# Main.net
KiCad netlist of a schematic drawn in Altium Designer
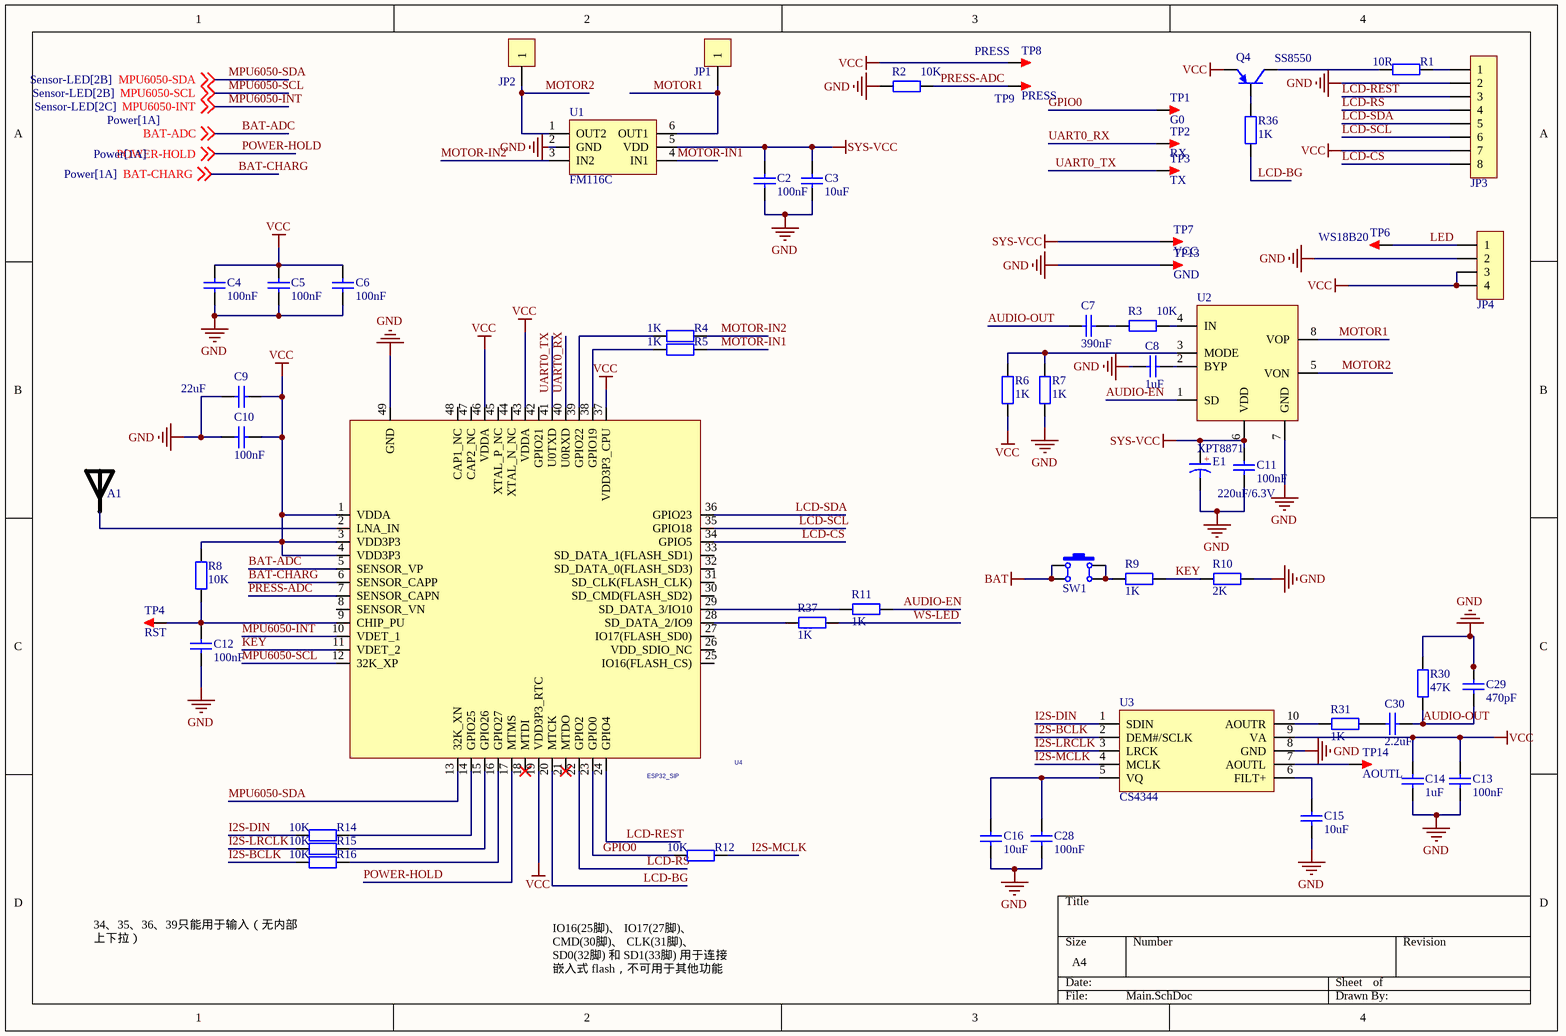
[diagram p0: Main.SchDoc]

(export (version "E")
  (design (tool "Eeschema 10.0.6"))
  (components
    (comp (ref "A1")
      (value "RAINSUN")
      (footprint "ANT-Rainsun-AN5120")
      (libsource (lib "1.7 - WiFi天线-SMA射频座") (part "ANT-Rainsun-AP5120"))
    )
    (comp (ref "C2")
      (value "100nF")
      (footprint "C0402_M")
      (description "贴片电容/MLCC电容")
      (libsource (lib "0.1 - 电阻-电容-电感-晶振-晶体-磁珠-电位器-法拉电容-馈通电容") (part "C"))
    )
    (comp (ref "C3")
      (value "10uF")
      (footprint "C0402_M")
      (description "贴片电容/MLCC电容")
      (libsource (lib "0.1 - 电阻-电容-电感-晶振-晶体-磁珠-电位器-法拉电容-馈通电容") (part "C"))
    )
    (comp (ref "C4")
      (value "100nF")
      (footprint "C0402_M")
      (description "贴片电容/MLCC电容")
      (libsource (lib "0.1 - 电阻-电容-电感-晶振-晶体-磁珠-电位器-法拉电容-馈通电容") (part "C"))
    )
    (comp (ref "C5")
      (value "100nF")
      (footprint "C0402_M")
      (description "贴片电容/MLCC电容")
      (libsource (lib "0.1 - 电阻-电容-电感-晶振-晶体-磁珠-电位器-法拉电容-馈通电容") (part "C"))
    )
    (comp (ref "C6")
      (value "100nF")
      (footprint "C0402_M")
      (description "贴片电容/MLCC电容")
      (libsource (lib "0.1 - 电阻-电容-电感-晶振-晶体-磁珠-电位器-法拉电容-馈通电容") (part "C"))
    )
    (comp (ref "C7")
      (value "390nF")
      (footprint "C0402_M")
      (description "贴片电容/MLCC电容")
      (libsource (lib "0.1 - 电阻-电容-电感-晶振-晶体-磁珠-电位器-法拉电容-馈通电容") (part "C"))
    )
    (comp (ref "C8")
      (value "1uF")
      (footprint "C0402_M")
      (description "贴片电容/MLCC电容")
      (libsource (lib "0.1 - 电阻-电容-电感-晶振-晶体-磁珠-电位器-法拉电容-馈通电容") (part "C"))
    )
    (comp (ref "C9")
      (value "22uF")
      (footprint "C0402_M")
      (description "贴片电容/MLCC电容")
      (libsource (lib "0.1 - 电阻-电容-电感-晶振-晶体-磁珠-电位器-法拉电容-馈通电容") (part "C"))
    )
    (comp (ref "C10")
      (value "100nF")
      (footprint "C0402_M")
      (description "贴片电容/MLCC电容")
      (libsource (lib "0.1 - 电阻-电容-电感-晶振-晶体-磁珠-电位器-法拉电容-馈通电容") (part "C"))
    )
    (comp (ref "C11")
      (value "100nF")
      (footprint "C0402_M")
      (description "贴片电容/MLCC电容")
      (libsource (lib "0.1 - 电阻-电容-电感-晶振-晶体-磁珠-电位器-法拉电容-馈通电容") (part "C"))
    )
    (comp (ref "C12")
      (value "100nF")
      (footprint "C0402_M")
      (description "贴片电容/MLCC电容")
      (libsource (lib "0.1 - 电阻-电容-电感-晶振-晶体-磁珠-电位器-法拉电容-馈通电容") (part "C"))
    )
    (comp (ref "C13")
      (value "100nF")
      (footprint "C0402_M")
      (description "贴片电容/MLCC电容")
      (libsource (lib "0.1 - 电阻-电容-电感-晶振-晶体-磁珠-电位器-法拉电容-馈通电容") (part "C"))
    )
    (comp (ref "C14")
      (value "1uF")
      (footprint "C0402_M")
      (description "贴片电容/MLCC电容")
      (libsource (lib "0.1 - 电阻-电容-电感-晶振-晶体-磁珠-电位器-法拉电容-馈通电容") (part "C"))
    )
    (comp (ref "C15")
      (value "10uF")
      (footprint "C0402_M")
      (description "贴片电容/MLCC电容")
      (libsource (lib "0.1 - 电阻-电容-电感-晶振-晶体-磁珠-电位器-法拉电容-馈通电容") (part "C"))
    )
    (comp (ref "C16")
      (value "10uF")
      (footprint "C0402_M")
      (description "贴片电容/MLCC电容")
      (libsource (lib "0.1 - 电阻-电容-电感-晶振-晶体-磁珠-电位器-法拉电容-馈通电容") (part "C"))
    )
    (comp (ref "C28")
      (value "100nF")
      (footprint "C0402_M")
      (description "贴片电容/MLCC电容")
      (libsource (lib "0.1 - 电阻-电容-电感-晶振-晶体-磁珠-电位器-法拉电容-馈通电容") (part "C"))
    )
    (comp (ref "C29")
      (value "470pF")
      (footprint "C0402_M")
      (description "贴片电容/MLCC电容")
      (libsource (lib "0.1 - 电阻-电容-电感-晶振-晶体-磁珠-电位器-法拉电容-馈通电容") (part "C"))
    )
    (comp (ref "C30")
      (value "2.2uF")
      (footprint "C0402_M")
      (description "贴片电容/MLCC电容")
      (libsource (lib "0.1 - 电阻-电容-电感-晶振-晶体-磁珠-电位器-法拉电容-馈通电容") (part "C"))
    )
    (comp (ref "E1")
      (value "220uF/6.3V")
      (footprint "C_3528")
      (description "贴片钽电容")
      (libsource (lib "0.1 - 电阻-电容-电感-晶振-晶体-磁珠-电位器-法拉电容-馈通电容") (part "CT"))
    )
    (comp (ref "JP1")
      (value "HDR-1x1")
      (footprint "HDR2.54-LI-1P")
      (description "1P接插件")
      (libsource (lib "5.5 - 2.54mm连接器(KF2EDGK_XH2.54_2.54排针排母)") (part "Header 1"))
    )
    (comp (ref "JP2")
      (value "HDR-1x1")
      (footprint "HDR2.54-LI-1P")
      (description "1P接插件")
      (libsource (lib "5.5 - 2.54mm连接器(KF2EDGK_XH2.54_2.54排针排母)") (part "Header 1"))
    )
    (comp (ref "JP3")
      (value "CON-8P")
      (footprint "FPC0.5-WT-8P-H1.0")
      (description "8P连接器")
      (libsource (lib "4.9 - 0.5mm连接器(FPC0.5)") (part "Header 8"))
    )
    (comp (ref "JP4")
      (value "CON-4P")
      (footprint "FPC0.5-WT-4P-H1.0")
      (description "4P连接器")
      (libsource (lib "4.9 - 0.5mm连接器(FPC0.5)") (part "Header 4"))
    )
    (comp (ref "Q4")
      (value "SS8550")
      (footprint "SOT23-3N")
      (description "高频放大-PNP型")
      (libsource (lib "0.4 - 三极管-场效应管-可控硅") (part "8550-SMD"))
    )
    (comp (ref "R1")
      (value "10R")
      (footprint "R0402_M")
      (description "贴片电阻")
      (libsource (lib "0.1 - 电阻-电容-电感-晶振-晶体-磁珠-电位器-法拉电容-馈通电容") (part "R"))
    )
    (comp (ref "R2")
      (value "10K")
      (footprint "R0402_M")
      (description "贴片电阻")
      (libsource (lib "0.1 - 电阻-电容-电感-晶振-晶体-磁珠-电位器-法拉电容-馈通电容") (part "R"))
    )
    (comp (ref "R3")
      (value "10K")
      (footprint "R0402_M")
      (description "贴片电阻")
      (libsource (lib "0.1 - 电阻-电容-电感-晶振-晶体-磁珠-电位器-法拉电容-馈通电容") (part "R"))
    )
    (comp (ref "R4")
      (value "1K")
      (footprint "R0402_M")
      (description "贴片电阻")
      (libsource (lib "0.1 - 电阻-电容-电感-晶振-晶体-磁珠-电位器-法拉电容-馈通电容") (part "R"))
    )
    (comp (ref "R5")
      (value "1K")
      (footprint "R0402_M")
      (description "贴片电阻")
      (libsource (lib "0.1 - 电阻-电容-电感-晶振-晶体-磁珠-电位器-法拉电容-馈通电容") (part "R"))
    )
    (comp (ref "R6")
      (value "1K")
      (footprint "R0402_M")
      (description "贴片电阻")
      (libsource (lib "0.1 - 电阻-电容-电感-晶振-晶体-磁珠-电位器-法拉电容-馈通电容") (part "R"))
    )
    (comp (ref "R7")
      (value "1K")
      (footprint "R0402_M")
      (description "贴片电阻")
      (libsource (lib "0.1 - 电阻-电容-电感-晶振-晶体-磁珠-电位器-法拉电容-馈通电容") (part "R"))
    )
    (comp (ref "R8")
      (value "10K")
      (footprint "R0402_M")
      (description "贴片电阻")
      (libsource (lib "0.1 - 电阻-电容-电感-晶振-晶体-磁珠-电位器-法拉电容-馈通电容") (part "R"))
    )
    (comp (ref "R9")
      (value "1K")
      (footprint "R0402_M")
      (description "贴片电阻")
      (libsource (lib "0.1 - 电阻-电容-电感-晶振-晶体-磁珠-电位器-法拉电容-馈通电容") (part "R"))
    )
    (comp (ref "R10")
      (value "2K")
      (footprint "R0402_M")
      (description "贴片电阻")
      (libsource (lib "0.1 - 电阻-电容-电感-晶振-晶体-磁珠-电位器-法拉电容-馈通电容") (part "R"))
    )
    (comp (ref "R11")
      (value "1K")
      (footprint "R0402_M")
      (description "贴片电阻")
      (libsource (lib "0.1 - 电阻-电容-电感-晶振-晶体-磁珠-电位器-法拉电容-馈通电容") (part "R"))
    )
    (comp (ref "R12")
      (value "10K")
      (footprint "R0402_M")
      (description "贴片电阻")
      (libsource (lib "0.1 - 电阻-电容-电感-晶振-晶体-磁珠-电位器-法拉电容-馈通电容") (part "R"))
    )
    (comp (ref "R14")
      (value "10K")
      (footprint "R0402_M")
      (description "贴片电阻")
      (libsource (lib "0.1 - 电阻-电容-电感-晶振-晶体-磁珠-电位器-法拉电容-馈通电容") (part "R"))
    )
    (comp (ref "R15")
      (value "10K")
      (footprint "R0402_M")
      (description "贴片电阻")
      (libsource (lib "0.1 - 电阻-电容-电感-晶振-晶体-磁珠-电位器-法拉电容-馈通电容") (part "R"))
    )
    (comp (ref "R16")
      (value "10K")
      (footprint "R0402_M")
      (description "贴片电阻")
      (libsource (lib "0.1 - 电阻-电容-电感-晶振-晶体-磁珠-电位器-法拉电容-馈通电容") (part "R"))
    )
    (comp (ref "R30")
      (value "47K")
      (footprint "R0402_M")
      (description "贴片电阻")
      (libsource (lib "0.1 - 电阻-电容-电感-晶振-晶体-磁珠-电位器-法拉电容-馈通电容") (part "R"))
    )
    (comp (ref "R31")
      (value "1K")
      (footprint "R0402_M")
      (description "贴片电阻")
      (libsource (lib "0.1 - 电阻-电容-电感-晶振-晶体-磁珠-电位器-法拉电容-馈通电容") (part "R"))
    )
    (comp (ref "R36")
      (value "1K")
      (footprint "R0402_M")
      (description "贴片电阻")
      (libsource (lib "0.1 - 电阻-电容-电感-晶振-晶体-磁珠-电位器-法拉电容-馈通电容") (part "R"))
    )
    (comp (ref "R37")
      (value "1K")
      (footprint "R0402_M")
      (description "贴片电阻")
      (libsource (lib "0.1 - 电阻-电容-电感-晶振-晶体-磁珠-电位器-法拉电容-馈通电容") (part "R"))
    )
    (comp (ref "SW1")
      (value "4x4x1.5")
      (footprint "SW SMD-4*4*1.5")
      (description "贴片4x4轻触开关")
      (libsource (lib "0.5 - 按键_开关_蜂鸣器_保险丝_电池_测试点_Mark点_铜柱") (part "SW SMD-4x4"))
    )
    (comp (ref "TP1")
      (value "G0")
      (footprint "TEST 1.2")
      (description "测试点")
      (libsource (lib "0.5 - 按键_开关_蜂鸣器_保险丝_电池_测试点_Mark点_铜柱") (part "TEST"))
    )
    (comp (ref "TP2")
      (value "RX")
      (footprint "TEST 1.2")
      (description "测试点")
      (libsource (lib "0.5 - 按键_开关_蜂鸣器_保险丝_电池_测试点_Mark点_铜柱") (part "TEST"))
    )
    (comp (ref "TP3")
      (value "TX")
      (footprint "TEST 1.2")
      (description "测试点")
      (libsource (lib "0.5 - 按键_开关_蜂鸣器_保险丝_电池_测试点_Mark点_铜柱") (part "TEST"))
    )
    (comp (ref "TP4")
      (value "RST")
      (footprint "TEST 1.2")
      (description "测试点")
      (libsource (lib "0.5 - 按键_开关_蜂鸣器_保险丝_电池_测试点_Mark点_铜柱") (part "TEST"))
    )
    (comp (ref "TP6")
      (value "WS18B20")
      (footprint "TEST 1.2")
      (description "测试点")
      (libsource (lib "0.5 - 按键_开关_蜂鸣器_保险丝_电池_测试点_Mark点_铜柱") (part "TEST"))
    )
    (comp (ref "TP7")
      (value "VCC")
      (footprint "TEST 1.2")
      (description "测试点")
      (libsource (lib "0.5 - 按键_开关_蜂鸣器_保险丝_电池_测试点_Mark点_铜柱") (part "TEST"))
    )
    (comp (ref "TP8")
      (value "PRESS")
      (footprint "TEST 1.2")
      (description "测试点")
      (libsource (lib "0.5 - 按键_开关_蜂鸣器_保险丝_电池_测试点_Mark点_铜柱") (part "TEST"))
    )
    (comp (ref "TP9")
      (value "PRESS")
      (footprint "TEST 1.2")
      (description "测试点")
      (libsource (lib "0.5 - 按键_开关_蜂鸣器_保险丝_电池_测试点_Mark点_铜柱") (part "TEST"))
    )
    (comp (ref "TP13")
      (value "GND")
      (footprint "TEST 1.2")
      (description "测试点")
      (libsource (lib "0.5 - 按键_开关_蜂鸣器_保险丝_电池_测试点_Mark点_铜柱") (part "TEST"))
    )
    (comp (ref "TP14")
      (value "AOUTL")
      (footprint "TEST 1.2")
      (description "测试点")
      (libsource (lib "0.5 - 按键_开关_蜂鸣器_保险丝_电池_测试点_Mark点_铜柱") (part "TEST"))
    )
    (comp (ref "U1")
      (value "FM116C")
      (footprint "SOT23-6")
      (description "电机驱动芯片")
      (libsource (lib "0.8 - 常见芯片") (part "FM116C"))
    )
    (comp (ref "U2")
      (value "XPT8871")
      (footprint "ESOP8_L")
      (description "A/B/D类功放")
      (libsource (lib "0.8 - 常见芯片") (part "XPT8871"))
    )
    (comp (ref "U3")
      (value "CS4344")
      (footprint "TSSOP-10_L3.0-W3.0-P0.50-LS4.9-BL")
      (description "10-Pin, 24-Bit, 192 kHz Stereo D/A Converter")
      (libsource (lib "0.8 - 常见芯片") (part "CS4344"))
    )
    (comp (ref "U4")
      (value "ESP32_SIP")
      (footprint "QFN48 7X7_N")
      (description "ESP32 PICO")
      (libsource (lib "3.11 - 乐鑫芯片") (part "ESP32-PICO"))
    )
  )
  (nets
    (net (code "1") (name "/AUDIO-EN") (class "Default")
      (node (ref "R11") (pin "2") (pinfunction "2_2") (pintype "passive"))
      (node (ref "U2") (pin "1") (pinfunction "SD_1") (pintype "passive"))
    )
    (net (code "2") (name "/AUDIO-OUT") (class "Default")
      (node (ref "C29") (pin "2") (pinfunction "2_2") (pintype "passive"))
      (node (ref "C30") (pin "2") (pinfunction "2_2") (pintype "passive"))
      (node (ref "C7") (pin "2") (pinfunction "2_2") (pintype "passive"))
      (node (ref "R30") (pin "2") (pinfunction "2_2") (pintype "passive"))
    )
    (net (code "3") (name "/GPIO0") (class "Default")
      (node (ref "R12") (pin "2") (pinfunction "2_2") (pintype "passive"))
      (node (ref "TP1") (pin "1") (pinfunction "1_1") (pintype "passive"))
      (node (ref "U4") (pin "23") (pinfunction "GPIO0_23") (pintype "passive"))
    )
    (net (code "4") (name "/I2S-BCLK") (class "Default")
      (node (ref "R16") (pin "2") (pinfunction "2_2") (pintype "passive"))
      (node (ref "U3") (pin "2") (pinfunction "DEM#/SCLK_2") (pintype "passive"))
    )
    (net (code "5") (name "/I2S-DIN") (class "Default")
      (node (ref "R14") (pin "2") (pinfunction "2_2") (pintype "passive"))
      (node (ref "U3") (pin "1") (pinfunction "SDIN_1") (pintype "passive"))
    )
    (net (code "6") (name "/I2S-LRCLK") (class "Default")
      (node (ref "R15") (pin "2") (pinfunction "2_2") (pintype "passive"))
      (node (ref "U3") (pin "3") (pinfunction "LRCK_3") (pintype "passive"))
    )
    (net (code "7") (name "/I2S-MCLK") (class "Default")
      (node (ref "R12") (pin "1") (pinfunction "1_1") (pintype "passive"))
      (node (ref "U3") (pin "4") (pinfunction "MCLK_4") (pintype "passive"))
    )
    (net (code "8") (name "/KEY") (class "Default")
      (node (ref "R10") (pin "1") (pinfunction "1_1") (pintype "passive"))
      (node (ref "R9") (pin "2") (pinfunction "2_2") (pintype "passive"))
      (node (ref "U4") (pin "11") (pinfunction "VDET_2_11") (pintype "passive"))
    )
    (net (code "9") (name "/LCD-BG") (class "Default")
      (node (ref "R36") (pin "2") (pinfunction "2_2") (pintype "passive"))
      (node (ref "U4") (pin "20") (pinfunction "MTCK_20") (pintype "passive"))
    )
    (net (code "10") (name "/LCD-CS") (class "Default")
      (node (ref "JP3") (pin "8") (pinfunction "8_8") (pintype "passive"))
      (node (ref "U4") (pin "34") (pinfunction "GPIO5_34") (pintype "passive"))
    )
    (net (code "11") (name "/LCD-REST") (class "Default")
      (node (ref "JP3") (pin "3") (pinfunction "3_3") (pintype "passive"))
      (node (ref "U4") (pin "24") (pinfunction "GPIO4_24") (pintype "passive"))
    )
    (net (code "12") (name "/LCD-RS") (class "Default")
      (node (ref "JP3") (pin "4") (pinfunction "4_4") (pintype "passive"))
      (node (ref "U4") (pin "22") (pinfunction "GPIO2_22") (pintype "passive"))
    )
    (net (code "13") (name "/LCD-SCL") (class "Default")
      (node (ref "JP3") (pin "6") (pinfunction "6_6") (pintype "passive"))
      (node (ref "U4") (pin "35") (pinfunction "GPIO18_35") (pintype "passive"))
    )
    (net (code "14") (name "/LCD-SDA") (class "Default")
      (node (ref "JP3") (pin "5") (pinfunction "5_5") (pintype "passive"))
      (node (ref "U4") (pin "36") (pinfunction "GPIO23_36") (pintype "passive"))
    )
    (net (code "15") (name "/LED") (class "Default")
      (node (ref "JP4") (pin "1") (pinfunction "1_1") (pintype "passive"))
      (node (ref "TP6") (pin "1") (pinfunction "1_1") (pintype "passive"))
    )
    (net (code "16") (name "/MOTOR-IN1") (class "Default")
      (node (ref "R5") (pin "1") (pinfunction "1_1") (pintype "passive"))
      (node (ref "U1") (pin "4") (pinfunction "IN1_4") (pintype "passive"))
    )
    (net (code "17") (name "/MOTOR-IN2") (class "Default")
      (node (ref "R4") (pin "1") (pinfunction "1_1") (pintype "passive"))
      (node (ref "U1") (pin "3") (pinfunction "IN2_3") (pintype "passive"))
    )
    (net (code "18") (name "/MOTOR1") (class "Default")
      (node (ref "JP1") (pin "1") (pinfunction "1_1") (pintype "passive"))
      (node (ref "U1") (pin "6") (pinfunction "OUT1_6") (pintype "passive"))
      (node (ref "U2") (pin "8") (pinfunction "VOP_8") (pintype "passive"))
    )
    (net (code "19") (name "/MOTOR2") (class "Default")
      (node (ref "JP2") (pin "1") (pinfunction "1_1") (pintype "passive"))
      (node (ref "U1") (pin "1") (pinfunction "OUT2_1") (pintype "passive"))
      (node (ref "U2") (pin "5") (pinfunction "VON_5") (pintype "passive"))
    )
    (net (code "20") (name "/PRESS-ADC") (class "Default")
      (node (ref "R2") (pin "2") (pinfunction "2_2") (pintype "passive"))
      (node (ref "TP9") (pin "1") (pinfunction "1_1") (pintype "passive"))
      (node (ref "U4") (pin "7") (pinfunction "SENSOR_CAPN_7") (pintype "passive"))
    )
    (net (code "21") (name "/UART0_RX") (class "Default")
      (node (ref "TP2") (pin "1") (pinfunction "1_1") (pintype "passive"))
      (node (ref "U4") (pin "40") (pinfunction "U0RXD_40") (pintype "power_in"))
    )
    (net (code "22") (name "/UART0_TX") (class "Default")
      (node (ref "TP3") (pin "1") (pinfunction "1_1") (pintype "passive"))
      (node (ref "U4") (pin "41") (pinfunction "U0TXD_41") (pintype "power_in"))
    )
    (net (code "23") (name "/WS-LED") (class "Default")
      (node (ref "R37") (pin "2") (pinfunction "2_2") (pintype "passive"))
    )
    (net (code "24") (name "BAT") (class "Default")
      (node (ref "SW1") (pin "1") (pinfunction "1_1") (pintype "passive"))
      (node (ref "SW1") (pin "4") (pinfunction "4_4") (pintype "passive"))
    )
    (net (code "25") (name "BAT-ADC") (class "Default")
      (node (ref "U4") (pin "5") (pinfunction "SENSOR_VP_5") (pintype "passive"))
    )
    (net (code "26") (name "BAT-CHARG") (class "Default")
      (node (ref "U4") (pin "6") (pinfunction "SENSOR_CAPP_6") (pintype "passive"))
    )
    (net (code "27") (name "GND") (class "Default")
      (node (ref "C10") (pin "2") (pinfunction "2_2") (pintype "passive"))
      (node (ref "C11") (pin "2") (pinfunction "2_2") (pintype "passive"))
      (node (ref "C12") (pin "1") (pinfunction "1_1") (pintype "passive"))
      (node (ref "C13") (pin "1") (pinfunction "1_1") (pintype "passive"))
      (node (ref "C14") (pin "1") (pinfunction "1_1") (pintype "passive"))
      (node (ref "C15") (pin "2") (pinfunction "2_2") (pintype "passive"))
      (node (ref "C16") (pin "2") (pinfunction "2_2") (pintype "passive"))
      (node (ref "C2") (pin "2") (pinfunction "2_2") (pintype "passive"))
      (node (ref "C28") (pin "2") (pinfunction "2_2") (pintype "passive"))
      (node (ref "C29") (pin "1") (pinfunction "1_1") (pintype "passive"))
      (node (ref "C3") (pin "2") (pinfunction "2_2") (pintype "passive"))
      (node (ref "C4") (pin "2") (pinfunction "2_2") (pintype "passive"))
      (node (ref "C5") (pin "2") (pinfunction "2_2") (pintype "passive"))
      (node (ref "C6") (pin "2") (pinfunction "2_2") (pintype "passive"))
      (node (ref "C8") (pin "2") (pinfunction "2_2") (pintype "passive"))
      (node (ref "C9") (pin "2") (pinfunction "2_2") (pintype "passive"))
      (node (ref "E1") (pin "2") (pinfunction "K_2") (pintype "passive"))
      (node (ref "JP3") (pin "2") (pinfunction "2_2") (pintype "passive"))
      (node (ref "JP4") (pin "2") (pinfunction "2_2") (pintype "passive"))
      (node (ref "R10") (pin "2") (pinfunction "2_2") (pintype "passive"))
      (node (ref "R2") (pin "1") (pinfunction "1_1") (pintype "passive"))
      (node (ref "R30") (pin "1") (pinfunction "1_1") (pintype "passive"))
      (node (ref "R7") (pin "2") (pinfunction "2_2") (pintype "passive"))
      (node (ref "TP13") (pin "1") (pinfunction "1_1") (pintype "passive"))
      (node (ref "U1") (pin "2") (pinfunction "GND_2") (pintype "passive"))
      (node (ref "U2") (pin "7") (pinfunction "GND_7") (pintype "passive"))
      (node (ref "U3") (pin "8") (pinfunction "GND_8") (pintype "passive"))
      (node (ref "U4") (pin "49") (pinfunction "GND_49") (pintype "power_in"))
    )
    (net (code "28") (name "MPU6050-INT") (class "Default")
      (node (ref "U4") (pin "10") (pinfunction "VDET_1_10") (pintype "passive"))
    )
    (net (code "29") (name "MPU6050-SCL") (class "Default")
      (node (ref "U4") (pin "12") (pinfunction "32K_XP_12") (pintype "passive"))
    )
    (net (code "30") (name "MPU6050-SDA") (class "Default")
      (node (ref "U4") (pin "13") (pinfunction "32K_XN_13") (pintype "passive"))
    )
    (net (code "31") (name "Net-(C7-Pad1)") (class "Default")
      (node (ref "C7") (pin "1") (pinfunction "1_1") (pintype "passive"))
      (node (ref "R3") (pin "1") (pinfunction "1_1") (pintype "passive"))
    )
    (net (code "32") (name "Net-(C30-Pad1)") (class "Default")
      (node (ref "C30") (pin "1") (pinfunction "1_1") (pintype "passive"))
      (node (ref "R31") (pin "2") (pinfunction "2_2") (pintype "passive"))
    )
    (net (code "33") (name "Net-(JP3-Pad1)") (class "Default")
      (node (ref "JP3") (pin "1") (pinfunction "1_1") (pintype "passive"))
      (node (ref "R1") (pin "1") (pinfunction "1_1") (pintype "passive"))
    )
    (net (code "34") (name "Net-(Q4-B)") (class "Default")
      (node (ref "Q4") (pin "1") (pinfunction "B_1") (pintype "passive"))
      (node (ref "R36") (pin "1") (pinfunction "1_1") (pintype "passive"))
    )
    (net (code "35") (name "Net-(Q4-C)") (class "Default")
      (node (ref "Q4") (pin "3") (pinfunction "C_3") (pintype "passive"))
      (node (ref "R1") (pin "2") (pinfunction "2_2") (pintype "passive"))
    )
    (net (code "36") (name "Net-(R9-Pad1)") (class "Default")
      (node (ref "R9") (pin "1") (pinfunction "1_1") (pintype "passive"))
      (node (ref "SW1") (pin "2") (pinfunction "2_2") (pintype "passive"))
      (node (ref "SW1") (pin "3") (pinfunction "3_3") (pintype "passive"))
    )
    (net (code "37") (name "Net-(U2-BYP)") (class "Default")
      (node (ref "C8") (pin "1") (pinfunction "1_1") (pintype "passive"))
      (node (ref "U2") (pin "2") (pinfunction "BYP_2") (pintype "passive"))
    )
    (net (code "38") (name "Net-(U2-IN)") (class "Default")
      (node (ref "R3") (pin "2") (pinfunction "2_2") (pintype "passive"))
      (node (ref "U2") (pin "4") (pinfunction "IN_4") (pintype "passive"))
    )
    (net (code "39") (name "Net-(U2-MODE)") (class "Default")
      (node (ref "R6") (pin "1") (pinfunction "1_1") (pintype "passive"))
      (node (ref "R7") (pin "1") (pinfunction "1_1") (pintype "passive"))
      (node (ref "U2") (pin "3") (pinfunction "MODE_3") (pintype "passive"))
    )
    (net (code "40") (name "Net-(U3-AOUTL)") (class "Default")
      (node (ref "TP14") (pin "1") (pinfunction "1_1") (pintype "passive"))
      (node (ref "U3") (pin "7") (pinfunction "AOUTL_7") (pintype "passive"))
    )
    (net (code "41") (name "Net-(U3-AOUTR)") (class "Default")
      (node (ref "R31") (pin "1") (pinfunction "1_1") (pintype "passive"))
      (node (ref "U3") (pin "10") (pinfunction "AOUTR_10") (pintype "passive"))
    )
    (net (code "42") (name "Net-(U3-FILT+)") (class "Default")
      (node (ref "C15") (pin "1") (pinfunction "1_1") (pintype "passive"))
      (node (ref "U3") (pin "6") (pinfunction "FILT+_6") (pintype "passive"))
    )
    (net (code "43") (name "Net-(U3-VQ)") (class "Default")
      (node (ref "C16") (pin "1") (pinfunction "1_1") (pintype "passive"))
      (node (ref "C28") (pin "1") (pinfunction "1_1") (pintype "passive"))
      (node (ref "U3") (pin "5") (pinfunction "VQ_5") (pintype "passive"))
    )
    (net (code "44") (name "Net-(U4-CHIP_PU)") (class "Default")
      (node (ref "C12") (pin "2") (pinfunction "2_2") (pintype "passive"))
      (node (ref "R8") (pin "1") (pinfunction "1_1") (pintype "passive"))
      (node (ref "TP4") (pin "1") (pinfunction "1_1") (pintype "passive"))
      (node (ref "U4") (pin "9") (pinfunction "CHIP_PU_9") (pintype "passive"))
    )
    (net (code "45") (name "Net-(U4-GPIO19)") (class "Default")
      (node (ref "R5") (pin "2") (pinfunction "2_2") (pintype "passive"))
      (node (ref "U4") (pin "38") (pinfunction "GPIO19_38") (pintype "passive"))
    )
    (net (code "46") (name "Net-(U4-GPIO22)") (class "Default")
      (node (ref "R4") (pin "2") (pinfunction "2_2") (pintype "passive"))
      (node (ref "U4") (pin "39") (pinfunction "GPIO22_39") (pintype "passive"))
    )
    (net (code "47") (name "Net-(U4-GPIO25)") (class "Default")
      (node (ref "R14") (pin "1") (pinfunction "1_1") (pintype "passive"))
      (node (ref "U4") (pin "14") (pinfunction "GPIO25_14") (pintype "passive"))
    )
    (net (code "48") (name "Net-(U4-GPIO26)") (class "Default")
      (node (ref "R15") (pin "1") (pinfunction "1_1") (pintype "passive"))
      (node (ref "U4") (pin "15") (pinfunction "GPIO26_15") (pintype "passive"))
    )
    (net (code "49") (name "Net-(U4-GPIO27)") (class "Default")
      (node (ref "R16") (pin "1") (pinfunction "1_1") (pintype "passive"))
      (node (ref "U4") (pin "16") (pinfunction "GPIO27_16") (pintype "passive"))
    )
    (net (code "50") (name "Net-(U4-LNA_IN)") (class "Default")
      (node (ref "A1") (pin "1") (pinfunction "1_1") (pintype "passive"))
      (node (ref "U4") (pin "2") (pinfunction "LNA_IN_2") (pintype "passive"))
    )
    (net (code "51") (name "Net-(U4-SD_DATA_2{slash}IO9)") (class "Default")
      (node (ref "R37") (pin "1") (pinfunction "1_1") (pintype "passive"))
      (node (ref "U4") (pin "28") (pinfunction "SD_DATA_2/IO9_28") (pintype "passive"))
    )
    (net (code "52") (name "Net-(U4-SD_DATA_3{slash}IO10)") (class "Default")
      (node (ref "R11") (pin "1") (pinfunction "1_1") (pintype "passive"))
      (node (ref "U4") (pin "29") (pinfunction "SD_DATA_3/IO10_29") (pintype "passive"))
    )
    (net (code "53") (name "POWER-HOLD") (class "Default")
      (node (ref "U4") (pin "17") (pinfunction "MTMS_17") (pintype "passive"))
    )
    (net (code "54") (name "SYS-VCC") (class "Default")
      (node (ref "C11") (pin "1") (pinfunction "1_1") (pintype "passive"))
      (node (ref "C2") (pin "1") (pinfunction "1_1") (pintype "passive"))
      (node (ref "C3") (pin "1") (pinfunction "1_1") (pintype "passive"))
      (node (ref "E1") (pin "1") (pinfunction "A_1") (pintype "passive"))
      (node (ref "TP7") (pin "1") (pinfunction "1_1") (pintype "passive"))
      (node (ref "U1") (pin "5") (pinfunction "VDD_5") (pintype "passive"))
      (node (ref "U2") (pin "6") (pinfunction "VDD_6") (pintype "passive"))
    )
    (net (code "55") (name "VCC") (class "Default")
      (node (ref "C10") (pin "1") (pinfunction "1_1") (pintype "passive"))
      (node (ref "C13") (pin "2") (pinfunction "2_2") (pintype "passive"))
      (node (ref "C14") (pin "2") (pinfunction "2_2") (pintype "passive"))
      (node (ref "C4") (pin "1") (pinfunction "1_1") (pintype "passive"))
      (node (ref "C5") (pin "1") (pinfunction "1_1") (pintype "passive"))
      (node (ref "C6") (pin "1") (pinfunction "1_1") (pintype "passive"))
      (node (ref "C9") (pin "1") (pinfunction "1_1") (pintype "passive"))
      (node (ref "JP3") (pin "7") (pinfunction "7_7") (pintype "passive"))
      (node (ref "JP4") (pin "3") (pinfunction "3_3") (pintype "passive"))
      (node (ref "JP4") (pin "4") (pinfunction "4_4") (pintype "passive"))
      (node (ref "Q4") (pin "2") (pinfunction "E_2") (pintype "passive"))
      (node (ref "R6") (pin "2") (pinfunction "2_2") (pintype "passive"))
      (node (ref "R8") (pin "2") (pinfunction "2_2") (pintype "passive"))
      (node (ref "TP8") (pin "1") (pinfunction "1_1") (pintype "passive"))
      (node (ref "U3") (pin "9") (pinfunction "VA_9") (pintype "passive"))
      (node (ref "U4") (pin "1") (pinfunction "VDDA_1") (pintype "power_in"))
      (node (ref "U4") (pin "19") (pinfunction "VDD3P3_RTC_19") (pintype "power_in"))
      (node (ref "U4") (pin "3") (pinfunction "VDD3P3_3") (pintype "power_in"))
      (node (ref "U4") (pin "37") (pinfunction "VDD3P3_CPU_37") (pintype "power_in"))
      (node (ref "U4") (pin "4") (pinfunction "VDD3P3_4") (pintype "power_in"))
      (node (ref "U4") (pin "43") (pinfunction "VDDA_43") (pintype "power_in"))
      (node (ref "U4") (pin "46") (pinfunction "VDDA_46") (pintype "power_in"))
    )
    (net (code "56") (name "unconnected-(U4-CAP1_NC-Pad48)") (class "Default")
      (node (ref "U4") (pin "48") (pinfunction "CAP1_NC_48") (pintype "passive"))
    )
    (net (code "57") (name "unconnected-(U4-CAP2_NC-Pad47)") (class "Default")
      (node (ref "U4") (pin "47") (pinfunction "CAP2_NC_47") (pintype "passive"))
    )
    (net (code "58") (name "unconnected-(U4-GPIO21-Pad42)") (class "Default")
      (node (ref "U4") (pin "42") (pinfunction "GPIO21_42") (pintype "passive"))
    )
    (net (code "59") (name "unconnected-(U4-IO16(FLASH_CS)-Pad25)") (class "Default")
      (node (ref "U4") (pin "25") (pinfunction "IO16(FLASH_CS)_25") (pintype "passive"))
    )
    (net (code "60") (name "unconnected-(U4-IO17(FLASH_SD0)-Pad27)") (class "Default")
      (node (ref "U4") (pin "27") (pinfunction "IO17(FLASH_SD0)_27") (pintype "passive"))
    )
    (net (code "61") (name "unconnected-(U4-MTDI-Pad18)") (class "Default")
      (node (ref "U4") (pin "18") (pinfunction "MTDI_18") (pintype "passive+no_connect"))
    )
    (net (code "62") (name "unconnected-(U4-MTDO-Pad21)") (class "Default")
      (node (ref "U4") (pin "21") (pinfunction "MTDO_21") (pintype "passive+no_connect"))
    )
    (net (code "63") (name "unconnected-(U4-SD_CLK(FLASH_CLK)-Pad31)") (class "Default")
      (node (ref "U4") (pin "31") (pinfunction "SD_CLK(FLASH_CLK)_31") (pintype "passive"))
    )
    (net (code "64") (name "unconnected-(U4-SD_CMD(FLASH_SD2)-Pad30)") (class "Default")
      (node (ref "U4") (pin "30") (pinfunction "SD_CMD(FLASH_SD2)_30") (pintype "passive"))
    )
    (net (code "65") (name "unconnected-(U4-SD_DATA_0(FLASH_SD3)-Pad32)") (class "Default")
      (node (ref "U4") (pin "32") (pinfunction "SD_DATA_0(FLASH_SD3)_32") (pintype "passive"))
    )
    (net (code "66") (name "unconnected-(U4-SD_DATA_1(FLASH_SD1)-Pad33)") (class "Default")
      (node (ref "U4") (pin "33") (pinfunction "SD_DATA_1(FLASH_SD1)_33") (pintype "passive"))
    )
    (net (code "67") (name "unconnected-(U4-SENSOR_VN-Pad8)") (class "Default")
      (node (ref "U4") (pin "8") (pinfunction "SENSOR_VN_8") (pintype "passive"))
    )
    (net (code "68") (name "unconnected-(U4-VDD_SDIO_NC-Pad26)") (class "Default")
      (node (ref "U4") (pin "26") (pinfunction "VDD_SDIO_NC_26") (pintype "passive"))
    )
    (net (code "69") (name "unconnected-(U4-XTAL_N_NC-Pad44)") (class "Default")
      (node (ref "U4") (pin "44") (pinfunction "XTAL_N_NC_44") (pintype "passive"))
    )
    (net (code "70") (name "unconnected-(U4-XTAL_P_NC-Pad45)") (class "Default")
      (node (ref "U4") (pin "45") (pinfunction "XTAL_P_NC_45") (pintype "passive"))
    )
  )
)
